# IziDAP-MainSheet.net
KiCad netlist of a schematic drawn in Altium Designer
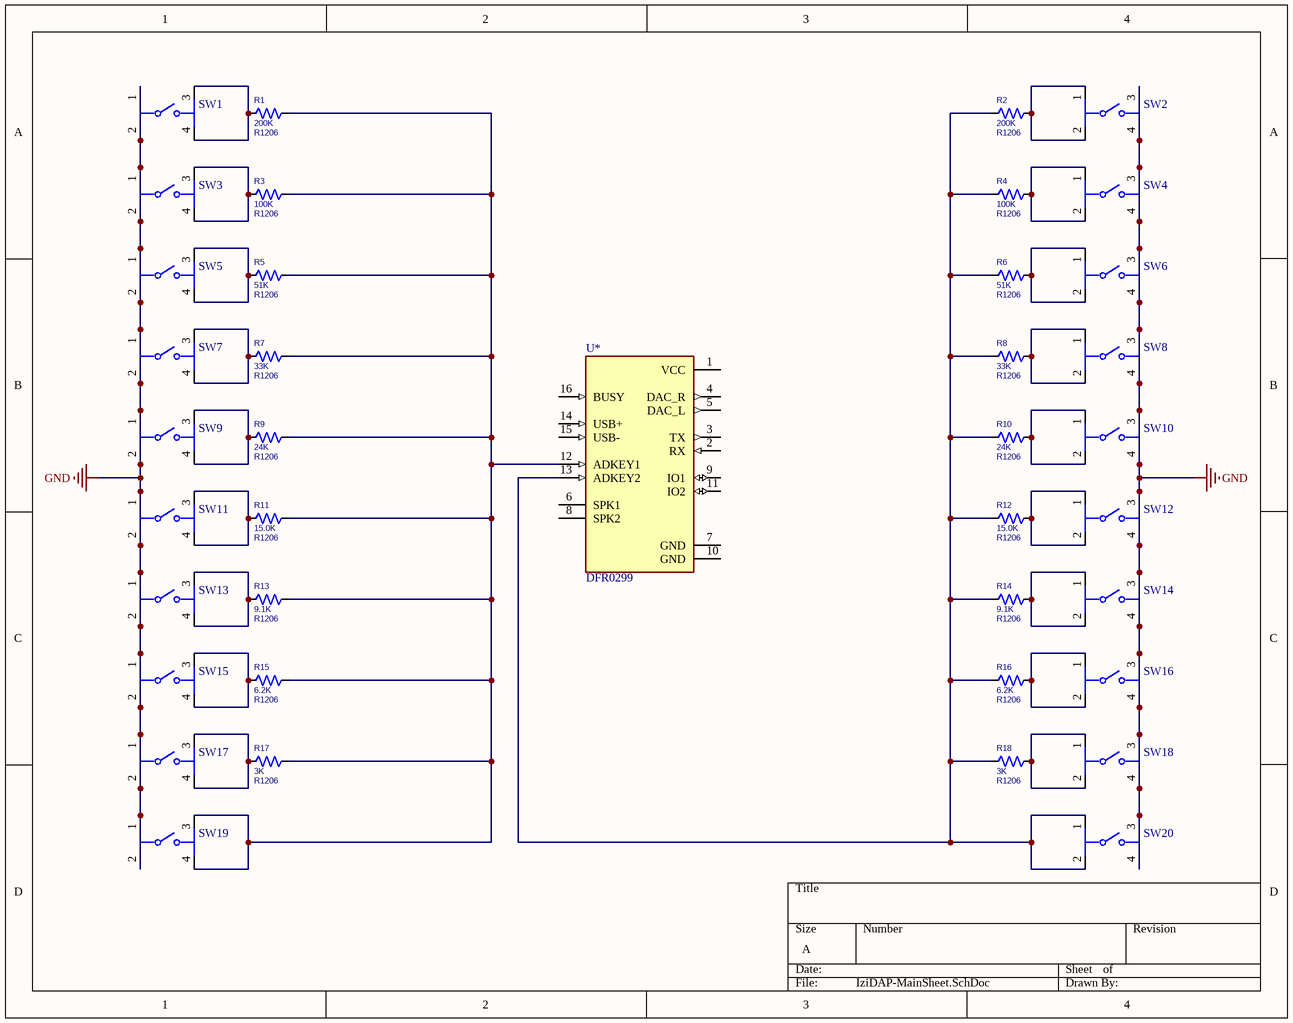
[diagram p0: IziDAP-MainSheet.SchDoc]

(export (version "E")
  (design (tool "Eeschema 10.0.6"))
  (components
    (comp (ref "R1")
      (value "200K")
      (footprint "RESC3216X84N")
      (description "RES, THICK FILM, SMT, 1/4W, 1%, RES1206, 200K")
      (fields
        (field (name "PACKAGE") "R1206")
        (field (name "TOLERANCE") "1%")
        (field (name "MANUFACTURER") "KOA-Speer Electronics, Inc.")
      )
      (libsource (lib "Avidyne") (part "Resistor"))
    )
    (comp (ref "R2")
      (value "200K")
      (footprint "RESC3216X84N")
      (description "RES, THICK FILM, SMT, 1/4W, 1%, RES1206, 200K")
      (fields
        (field (name "PACKAGE") "R1206")
        (field (name "TOLERANCE") "1%")
        (field (name "MANUFACTURER") "KOA-Speer Electronics, Inc.")
      )
      (libsource (lib "Avidyne") (part "Resistor"))
    )
    (comp (ref "R3")
      (value "100K")
      (footprint "RESC3216X84N")
      (description "RES, THICK FILM CHIP, SMT, 1/8W, 1%, RES1206, 100K OHM")
      (fields
        (field (name "PACKAGE") "R1206")
        (field (name "TOLERANCE") "1%")
        (field (name "MANUFACTURER") "Panasonic Electronic Devices, Corp.")
      )
      (libsource (lib "Avidyne") (part "Resistor"))
    )
    (comp (ref "R4")
      (value "100K")
      (footprint "RESC3216X84N")
      (description "RES, THICK FILM CHIP, SMT, 1/8W, 1%, RES1206, 100K OHM")
      (fields
        (field (name "PACKAGE") "R1206")
        (field (name "TOLERANCE") "1%")
        (field (name "MANUFACTURER") "Panasonic Electronic Devices, Corp.")
      )
      (libsource (lib "Avidyne") (part "Resistor"))
    )
    (comp (ref "R5")
      (value "51K")
      (footprint "RESC3216X84N")
      (description "RES, THICK FILM, SMT, 1/8W, 5%, 1206, 51K OHM")
      (fields
        (field (name "PACKAGE") "R1206")
        (field (name "TOLERANCE") "5%")
        (field (name "MANUFACTURER") "Vishay-Dale Intertechnology, Inc")
      )
      (libsource (lib "Avidyne") (part "Resistor"))
    )
    (comp (ref "R6")
      (value "51K")
      (footprint "RESC3216X84N")
      (description "RES, THICK FILM, SMT, 1/8W, 5%, 1206, 51K OHM")
      (fields
        (field (name "PACKAGE") "R1206")
        (field (name "TOLERANCE") "5%")
        (field (name "MANUFACTURER") "Vishay-Dale Intertechnology, Inc")
      )
      (libsource (lib "Avidyne") (part "Resistor"))
    )
    (comp (ref "R7")
      (value "33K")
      (footprint "RESC3216X84N")
      (description "RES, 1/8W, 1%, 1206, 33K OHM")
      (fields
        (field (name "PACKAGE") "R1206")
        (field (name "TOLERANCE") "1%")
        (field (name "MANUFACTURER") "Panasonic Electronic Devices, Corp.")
      )
      (libsource (lib "altium-import") (part "root_1_Resistor_"))
    )
    (comp (ref "R8")
      (value "33K")
      (footprint "RESC3216X84N")
      (description "RES, 1/8W, 1%, 1206, 33K OHM")
      (fields
        (field (name "PACKAGE") "R1206")
        (field (name "TOLERANCE") "1%")
        (field (name "MANUFACTURER") "Panasonic Electronic Devices, Corp.")
      )
      (libsource (lib "altium-import") (part "root_1_Resistor_"))
    )
    (comp (ref "R9")
      (value "24K")
      (footprint "RESC3216X84N")
      (description "RES, 1/8W, 1%, 1206, 24K OHM")
      (fields
        (field (name "PACKAGE") "R1206")
        (field (name "TOLERANCE") "1%")
        (field (name "MANUFACTURER") "Panasonic Electronic Devices, Corp.")
      )
      (libsource (lib "altium-import") (part "root_1_Resistor_"))
    )
    (comp (ref "R10")
      (value "24K")
      (footprint "RESC3216X84N")
      (description "RES, 1/8W, 1%, 1206, 24K OHM")
      (fields
        (field (name "PACKAGE") "R1206")
        (field (name "TOLERANCE") "1%")
        (field (name "MANUFACTURER") "Panasonic Electronic Devices, Corp.")
      )
      (libsource (lib "altium-import") (part "root_1_Resistor_"))
    )
    (comp (ref "R11")
      (value "15.0K")
      (footprint "RESC3216X84N")
      (description "RES, 1/8W, 1%, 1206, 15.0K OHM")
      (fields
        (field (name "PACKAGE") "R1206")
        (field (name "TOLERANCE") "1%")
        (field (name "MANUFACTURER") "Panasonic Electronic Devices, Corp.")
      )
      (libsource (lib "Avidyne") (part "Resistor"))
    )
    (comp (ref "R12")
      (value "15.0K")
      (footprint "RESC3216X84N")
      (description "RES, 1/8W, 1%, 1206, 15.0K OHM")
      (fields
        (field (name "PACKAGE") "R1206")
        (field (name "TOLERANCE") "1%")
        (field (name "MANUFACTURER") "Panasonic Electronic Devices, Corp.")
      )
      (libsource (lib "Avidyne") (part "Resistor"))
    )
    (comp (ref "R13")
      (value "9.1K")
      (footprint "RESC3216X84N")
      (description "RES, 1/8W, 1%, 1206, 9.1K OHM")
      (fields
        (field (name "PACKAGE") "R1206")
        (field (name "TOLERANCE") "1%")
        (field (name "MANUFACTURER") "Panasonic Electronic Devices, Corp.")
      )
      (libsource (lib "altium-import") (part "root_1_Resistor_"))
    )
    (comp (ref "R14")
      (value "9.1K")
      (footprint "RESC3216X84N")
      (description "RES, 1/8W, 1%, 1206, 9.1K OHM")
      (fields
        (field (name "PACKAGE") "R1206")
        (field (name "TOLERANCE") "1%")
        (field (name "MANUFACTURER") "Panasonic Electronic Devices, Corp.")
      )
      (libsource (lib "altium-import") (part "root_1_Resistor_"))
    )
    (comp (ref "R15")
      (value "6.2K")
      (footprint "RESC3216X84N")
      (description "RES, 1/8W, 1%, 1206, 6.2K OHM")
      (fields
        (field (name "PACKAGE") "R1206")
        (field (name "TOLERANCE") "1%")
        (field (name "MANUFACTURER") "Panasonic Electronic Devices, Corp.")
      )
      (libsource (lib "altium-import") (part "root_1_Resistor_"))
    )
    (comp (ref "R16")
      (value "6.2K")
      (footprint "RESC3216X84N")
      (description "RES, 1/8W, 1%, 1206, 6.2K OHM")
      (fields
        (field (name "PACKAGE") "R1206")
        (field (name "TOLERANCE") "1%")
        (field (name "MANUFACTURER") "Panasonic Electronic Devices, Corp.")
      )
      (libsource (lib "altium-import") (part "root_1_Resistor_"))
    )
    (comp (ref "R17")
      (value "3K")
      (footprint "RESC3216X84N")
      (description "RES, 1/8W, 1%, 1206, 3K OHM")
      (fields
        (field (name "PACKAGE") "R1206")
        (field (name "TOLERANCE") "1%")
        (field (name "MANUFACTURER") "Panasonic Electronic Devices, Corp.")
      )
      (libsource (lib "altium-import") (part "root_1_Resistor_"))
    )
    (comp (ref "R18")
      (value "3K")
      (footprint "RESC3216X84N")
      (description "RES, 1/8W, 1%, 1206, 3K OHM")
      (fields
        (field (name "PACKAGE") "R1206")
        (field (name "TOLERANCE") "1%")
        (field (name "MANUFACTURER") "Panasonic Electronic Devices, Corp.")
      )
      (libsource (lib "altium-import") (part "root_1_Resistor_"))
    )
    (comp (ref "SW1")
      (value "2-1825910-6")
      (footprint "FP-2-1825910-6-MFG")
      (description "SWITCH TACTILE SPST-NO 0.05A 24V")
      (libsource (lib "Altium Content Vault") (part "b8895f3f4cefb76e1819d2863dba89b"))
    )
    (comp (ref "SW2")
      (value "2-1825910-6")
      (footprint "FP-2-1825910-6-MFG")
      (description "SWITCH TACTILE SPST-NO 0.05A 24V")
      (libsource (lib "Altium Content Vault") (part "b8895f3f4cefb76e1819d2863dba89b"))
    )
    (comp (ref "SW3")
      (value "2-1825910-6")
      (footprint "FP-2-1825910-6-MFG")
      (description "SWITCH TACTILE SPST-NO 0.05A 24V")
      (libsource (lib "Altium Content Vault") (part "b8895f3f4cefb76e1819d2863dba89b"))
    )
    (comp (ref "SW4")
      (value "2-1825910-6")
      (footprint "FP-2-1825910-6-MFG")
      (description "SWITCH TACTILE SPST-NO 0.05A 24V")
      (libsource (lib "Altium Content Vault") (part "b8895f3f4cefb76e1819d2863dba89b"))
    )
    (comp (ref "SW5")
      (value "2-1825910-6")
      (footprint "FP-2-1825910-6-MFG")
      (description "SWITCH TACTILE SPST-NO 0.05A 24V")
      (libsource (lib "Altium Content Vault") (part "b8895f3f4cefb76e1819d2863dba89b"))
    )
    (comp (ref "SW6")
      (value "2-1825910-6")
      (footprint "FP-2-1825910-6-MFG")
      (description "SWITCH TACTILE SPST-NO 0.05A 24V")
      (libsource (lib "Altium Content Vault") (part "b8895f3f4cefb76e1819d2863dba89b"))
    )
    (comp (ref "SW7")
      (value "2-1825910-6")
      (footprint "FP-2-1825910-6-MFG")
      (description "SWITCH TACTILE SPST-NO 0.05A 24V")
      (libsource (lib "Altium Content Vault") (part "b8895f3f4cefb76e1819d2863dba89b"))
    )
    (comp (ref "SW8")
      (value "2-1825910-6")
      (footprint "FP-2-1825910-6-MFG")
      (description "SWITCH TACTILE SPST-NO 0.05A 24V")
      (libsource (lib "Altium Content Vault") (part "b8895f3f4cefb76e1819d2863dba89b"))
    )
    (comp (ref "SW9")
      (value "2-1825910-6")
      (footprint "FP-2-1825910-6-MFG")
      (description "SWITCH TACTILE SPST-NO 0.05A 24V")
      (libsource (lib "Altium Content Vault") (part "b8895f3f4cefb76e1819d2863dba89b"))
    )
    (comp (ref "SW10")
      (value "2-1825910-6")
      (footprint "FP-2-1825910-6-MFG")
      (description "SWITCH TACTILE SPST-NO 0.05A 24V")
      (libsource (lib "Altium Content Vault") (part "b8895f3f4cefb76e1819d2863dba89b"))
    )
    (comp (ref "SW11")
      (value "2-1825910-6")
      (footprint "FP-2-1825910-6-MFG")
      (description "SWITCH TACTILE SPST-NO 0.05A 24V")
      (libsource (lib "Altium Content Vault") (part "b8895f3f4cefb76e1819d2863dba89b"))
    )
    (comp (ref "SW12")
      (value "2-1825910-6")
      (footprint "FP-2-1825910-6-MFG")
      (description "SWITCH TACTILE SPST-NO 0.05A 24V")
      (libsource (lib "Altium Content Vault") (part "b8895f3f4cefb76e1819d2863dba89b"))
    )
    (comp (ref "SW13")
      (value "2-1825910-6")
      (footprint "FP-2-1825910-6-MFG")
      (description "SWITCH TACTILE SPST-NO 0.05A 24V")
      (libsource (lib "Altium Content Vault") (part "b8895f3f4cefb76e1819d2863dba89b"))
    )
    (comp (ref "SW14")
      (value "2-1825910-6")
      (footprint "FP-2-1825910-6-MFG")
      (description "SWITCH TACTILE SPST-NO 0.05A 24V")
      (libsource (lib "Altium Content Vault") (part "b8895f3f4cefb76e1819d2863dba89b"))
    )
    (comp (ref "SW15")
      (value "2-1825910-6")
      (footprint "FP-2-1825910-6-MFG")
      (description "SWITCH TACTILE SPST-NO 0.05A 24V")
      (libsource (lib "Altium Content Vault") (part "b8895f3f4cefb76e1819d2863dba89b"))
    )
    (comp (ref "SW16")
      (value "2-1825910-6")
      (footprint "FP-2-1825910-6-MFG")
      (description "SWITCH TACTILE SPST-NO 0.05A 24V")
      (libsource (lib "Altium Content Vault") (part "b8895f3f4cefb76e1819d2863dba89b"))
    )
    (comp (ref "SW17")
      (value "2-1825910-6")
      (footprint "FP-2-1825910-6-MFG")
      (description "SWITCH TACTILE SPST-NO 0.05A 24V")
      (libsource (lib "Altium Content Vault") (part "b8895f3f4cefb76e1819d2863dba89b"))
    )
    (comp (ref "SW18")
      (value "2-1825910-6")
      (footprint "FP-2-1825910-6-MFG")
      (description "SWITCH TACTILE SPST-NO 0.05A 24V")
      (libsource (lib "Altium Content Vault") (part "b8895f3f4cefb76e1819d2863dba89b"))
    )
    (comp (ref "SW19")
      (value "2-1825910-6")
      (footprint "FP-2-1825910-6-MFG")
      (description "SWITCH TACTILE SPST-NO 0.05A 24V")
      (libsource (lib "Altium Content Vault") (part "b8895f3f4cefb76e1819d2863dba89b"))
    )
    (comp (ref "SW20")
      (value "2-1825910-6")
      (footprint "FP-2-1825910-6-MFG")
      (description "SWITCH TACTILE SPST-NO 0.05A 24V")
      (libsource (lib "Altium Content Vault") (part "b8895f3f4cefb76e1819d2863dba89b"))
    )
    (comp (ref "U*")
      (value "DFR0299")
      (footprint "DFR0299")
      (description "DFRobot DFR0299 DFPlayer - A Mini MP3 Player For Arduino")
      (fields (field (name "MANUFACTURER") "DFRobot"))
      (libsource (lib "Modules") (part "DFR0299"))
    )
  )
  (nets
    (net (code "1") (name "GND") (class "Default")
      (node (ref "SW1") (pin "1") (pinfunction "1_1") (pintype "passive"))
      (node (ref "SW1") (pin "2") (pinfunction "2_2") (pintype "passive"))
      (node (ref "SW10") (pin "3") (pinfunction "3_3") (pintype "passive"))
      (node (ref "SW10") (pin "4") (pinfunction "4_4") (pintype "passive"))
      (node (ref "SW11") (pin "1") (pinfunction "1_1") (pintype "passive"))
      (node (ref "SW11") (pin "2") (pinfunction "2_2") (pintype "passive"))
      (node (ref "SW12") (pin "3") (pinfunction "3_3") (pintype "passive"))
      (node (ref "SW12") (pin "4") (pinfunction "4_4") (pintype "passive"))
      (node (ref "SW13") (pin "1") (pinfunction "1_1") (pintype "passive"))
      (node (ref "SW13") (pin "2") (pinfunction "2_2") (pintype "passive"))
      (node (ref "SW14") (pin "3") (pinfunction "3_3") (pintype "passive"))
      (node (ref "SW14") (pin "4") (pinfunction "4_4") (pintype "passive"))
      (node (ref "SW15") (pin "1") (pinfunction "1_1") (pintype "passive"))
      (node (ref "SW15") (pin "2") (pinfunction "2_2") (pintype "passive"))
      (node (ref "SW16") (pin "3") (pinfunction "3_3") (pintype "passive"))
      (node (ref "SW16") (pin "4") (pinfunction "4_4") (pintype "passive"))
      (node (ref "SW17") (pin "1") (pinfunction "1_1") (pintype "passive"))
      (node (ref "SW17") (pin "2") (pinfunction "2_2") (pintype "passive"))
      (node (ref "SW18") (pin "3") (pinfunction "3_3") (pintype "passive"))
      (node (ref "SW18") (pin "4") (pinfunction "4_4") (pintype "passive"))
      (node (ref "SW19") (pin "1") (pinfunction "1_1") (pintype "passive"))
      (node (ref "SW19") (pin "2") (pinfunction "2_2") (pintype "passive"))
      (node (ref "SW2") (pin "3") (pinfunction "3_3") (pintype "passive"))
      (node (ref "SW2") (pin "4") (pinfunction "4_4") (pintype "passive"))
      (node (ref "SW20") (pin "3") (pinfunction "3_3") (pintype "passive"))
      (node (ref "SW20") (pin "4") (pinfunction "4_4") (pintype "passive"))
      (node (ref "SW3") (pin "1") (pinfunction "1_1") (pintype "passive"))
      (node (ref "SW3") (pin "2") (pinfunction "2_2") (pintype "passive"))
      (node (ref "SW4") (pin "3") (pinfunction "3_3") (pintype "passive"))
      (node (ref "SW4") (pin "4") (pinfunction "4_4") (pintype "passive"))
      (node (ref "SW5") (pin "1") (pinfunction "1_1") (pintype "passive"))
      (node (ref "SW5") (pin "2") (pinfunction "2_2") (pintype "passive"))
      (node (ref "SW6") (pin "3") (pinfunction "3_3") (pintype "passive"))
      (node (ref "SW6") (pin "4") (pinfunction "4_4") (pintype "passive"))
      (node (ref "SW7") (pin "1") (pinfunction "1_1") (pintype "passive"))
      (node (ref "SW7") (pin "2") (pinfunction "2_2") (pintype "passive"))
      (node (ref "SW8") (pin "3") (pinfunction "3_3") (pintype "passive"))
      (node (ref "SW8") (pin "4") (pinfunction "4_4") (pintype "passive"))
      (node (ref "SW9") (pin "1") (pinfunction "1_1") (pintype "passive"))
      (node (ref "SW9") (pin "2") (pinfunction "2_2") (pintype "passive"))
    )
    (net (code "2") (name "Net-(R1-Pad1)") (class "Default")
      (node (ref "R1") (pin "1") (pinfunction "1_1") (pintype "passive"))
      (node (ref "SW1") (pin "3") (pinfunction "3_3") (pintype "passive"))
      (node (ref "SW1") (pin "4") (pinfunction "4_4") (pintype "passive"))
    )
    (net (code "3") (name "Net-(R2-Pad2)") (class "Default")
      (node (ref "R2") (pin "2") (pinfunction "2_2") (pintype "passive"))
      (node (ref "SW2") (pin "1") (pinfunction "1_1") (pintype "passive"))
      (node (ref "SW2") (pin "2") (pinfunction "2_2") (pintype "passive"))
    )
    (net (code "4") (name "Net-(R3-Pad1)") (class "Default")
      (node (ref "R3") (pin "1") (pinfunction "1_1") (pintype "passive"))
      (node (ref "SW3") (pin "3") (pinfunction "3_3") (pintype "passive"))
      (node (ref "SW3") (pin "4") (pinfunction "4_4") (pintype "passive"))
    )
    (net (code "5") (name "Net-(R4-Pad2)") (class "Default")
      (node (ref "R4") (pin "2") (pinfunction "2_2") (pintype "passive"))
      (node (ref "SW4") (pin "1") (pinfunction "1_1") (pintype "passive"))
      (node (ref "SW4") (pin "2") (pinfunction "2_2") (pintype "passive"))
    )
    (net (code "6") (name "Net-(R5-Pad1)") (class "Default")
      (node (ref "R5") (pin "1") (pinfunction "1_1") (pintype "passive"))
      (node (ref "SW5") (pin "3") (pinfunction "3_3") (pintype "passive"))
      (node (ref "SW5") (pin "4") (pinfunction "4_4") (pintype "passive"))
    )
    (net (code "7") (name "Net-(R6-Pad2)") (class "Default")
      (node (ref "R6") (pin "2") (pinfunction "2_2") (pintype "passive"))
      (node (ref "SW6") (pin "1") (pinfunction "1_1") (pintype "passive"))
      (node (ref "SW6") (pin "2") (pinfunction "2_2") (pintype "passive"))
    )
    (net (code "8") (name "Net-(R7-Pad1)") (class "Default")
      (node (ref "R7") (pin "1") (pinfunction "1_1") (pintype "passive"))
      (node (ref "SW7") (pin "3") (pinfunction "3_3") (pintype "passive"))
      (node (ref "SW7") (pin "4") (pinfunction "4_4") (pintype "passive"))
    )
    (net (code "9") (name "Net-(R8-Pad2)") (class "Default")
      (node (ref "R8") (pin "2") (pinfunction "2_2") (pintype "passive"))
      (node (ref "SW8") (pin "1") (pinfunction "1_1") (pintype "passive"))
      (node (ref "SW8") (pin "2") (pinfunction "2_2") (pintype "passive"))
    )
    (net (code "10") (name "Net-(R9-Pad1)") (class "Default")
      (node (ref "R9") (pin "1") (pinfunction "1_1") (pintype "passive"))
      (node (ref "SW9") (pin "3") (pinfunction "3_3") (pintype "passive"))
      (node (ref "SW9") (pin "4") (pinfunction "4_4") (pintype "passive"))
    )
    (net (code "11") (name "Net-(R10-Pad2)") (class "Default")
      (node (ref "R10") (pin "2") (pinfunction "2_2") (pintype "passive"))
      (node (ref "SW10") (pin "1") (pinfunction "1_1") (pintype "passive"))
      (node (ref "SW10") (pin "2") (pinfunction "2_2") (pintype "passive"))
    )
    (net (code "12") (name "Net-(R11-Pad1)") (class "Default")
      (node (ref "R11") (pin "1") (pinfunction "1_1") (pintype "passive"))
      (node (ref "SW11") (pin "3") (pinfunction "3_3") (pintype "passive"))
      (node (ref "SW11") (pin "4") (pinfunction "4_4") (pintype "passive"))
    )
    (net (code "13") (name "Net-(R12-Pad2)") (class "Default")
      (node (ref "R12") (pin "2") (pinfunction "2_2") (pintype "passive"))
      (node (ref "SW12") (pin "1") (pinfunction "1_1") (pintype "passive"))
      (node (ref "SW12") (pin "2") (pinfunction "2_2") (pintype "passive"))
    )
    (net (code "14") (name "Net-(R13-Pad1)") (class "Default")
      (node (ref "R13") (pin "1") (pinfunction "1_1") (pintype "passive"))
      (node (ref "SW13") (pin "3") (pinfunction "3_3") (pintype "passive"))
      (node (ref "SW13") (pin "4") (pinfunction "4_4") (pintype "passive"))
    )
    (net (code "15") (name "Net-(R14-Pad2)") (class "Default")
      (node (ref "R14") (pin "2") (pinfunction "2_2") (pintype "passive"))
      (node (ref "SW14") (pin "1") (pinfunction "1_1") (pintype "passive"))
      (node (ref "SW14") (pin "2") (pinfunction "2_2") (pintype "passive"))
    )
    (net (code "16") (name "Net-(R15-Pad1)") (class "Default")
      (node (ref "R15") (pin "1") (pinfunction "1_1") (pintype "passive"))
      (node (ref "SW15") (pin "3") (pinfunction "3_3") (pintype "passive"))
      (node (ref "SW15") (pin "4") (pinfunction "4_4") (pintype "passive"))
    )
    (net (code "17") (name "Net-(R16-Pad2)") (class "Default")
      (node (ref "R16") (pin "2") (pinfunction "2_2") (pintype "passive"))
      (node (ref "SW16") (pin "1") (pinfunction "1_1") (pintype "passive"))
      (node (ref "SW16") (pin "2") (pinfunction "2_2") (pintype "passive"))
    )
    (net (code "18") (name "Net-(R17-Pad1)") (class "Default")
      (node (ref "R17") (pin "1") (pinfunction "1_1") (pintype "passive"))
      (node (ref "SW17") (pin "3") (pinfunction "3_3") (pintype "passive"))
      (node (ref "SW17") (pin "4") (pinfunction "4_4") (pintype "passive"))
    )
    (net (code "19") (name "Net-(R18-Pad2)") (class "Default")
      (node (ref "R18") (pin "2") (pinfunction "2_2") (pintype "passive"))
      (node (ref "SW18") (pin "1") (pinfunction "1_1") (pintype "passive"))
      (node (ref "SW18") (pin "2") (pinfunction "2_2") (pintype "passive"))
    )
    (net (code "20") (name "Net-(U*-ADKEY1)") (class "Default")
      (node (ref "R1") (pin "2") (pinfunction "2_2") (pintype "passive"))
      (node (ref "R11") (pin "2") (pinfunction "2_2") (pintype "passive"))
      (node (ref "R13") (pin "2") (pinfunction "2_2") (pintype "passive"))
      (node (ref "R15") (pin "2") (pinfunction "2_2") (pintype "passive"))
      (node (ref "R17") (pin "2") (pinfunction "2_2") (pintype "passive"))
      (node (ref "R3") (pin "2") (pinfunction "2_2") (pintype "passive"))
      (node (ref "R5") (pin "2") (pinfunction "2_2") (pintype "passive"))
      (node (ref "R7") (pin "2") (pinfunction "2_2") (pintype "passive"))
      (node (ref "R9") (pin "2") (pinfunction "2_2") (pintype "passive"))
      (node (ref "SW19") (pin "3") (pinfunction "3_3") (pintype "passive"))
      (node (ref "SW19") (pin "4") (pinfunction "4_4") (pintype "passive"))
      (node (ref "U*") (pin "12") (pinfunction "ADKEY1_12") (pintype "input"))
    )
    (net (code "21") (name "Net-(U*-ADKEY2)") (class "Default")
      (node (ref "R10") (pin "1") (pinfunction "1_1") (pintype "passive"))
      (node (ref "R12") (pin "1") (pinfunction "1_1") (pintype "passive"))
      (node (ref "R14") (pin "1") (pinfunction "1_1") (pintype "passive"))
      (node (ref "R16") (pin "1") (pinfunction "1_1") (pintype "passive"))
      (node (ref "R18") (pin "1") (pinfunction "1_1") (pintype "passive"))
      (node (ref "R2") (pin "1") (pinfunction "1_1") (pintype "passive"))
      (node (ref "R4") (pin "1") (pinfunction "1_1") (pintype "passive"))
      (node (ref "R6") (pin "1") (pinfunction "1_1") (pintype "passive"))
      (node (ref "R8") (pin "1") (pinfunction "1_1") (pintype "passive"))
      (node (ref "SW20") (pin "1") (pinfunction "1_1") (pintype "passive"))
      (node (ref "SW20") (pin "2") (pinfunction "2_2") (pintype "passive"))
      (node (ref "U*") (pin "13") (pinfunction "ADKEY2_13") (pintype "input"))
    )
    (net (code "22") (name "unconnected-(U*-BUSY-Pad16)") (class "Default")
      (node (ref "U*") (pin "16") (pinfunction "BUSY_16") (pintype "input"))
    )
    (net (code "23") (name "unconnected-(U*-DAC_L-Pad5)") (class "Default")
      (node (ref "U*") (pin "5") (pinfunction "DAC_L_5") (pintype "output"))
    )
    (net (code "24") (name "unconnected-(U*-DAC_R-Pad4)") (class "Default")
      (node (ref "U*") (pin "4") (pinfunction "DAC_R_4") (pintype "output"))
    )
    (net (code "25") (name "unconnected-(U*-GND-Pad7)") (class "Default")
      (node (ref "U*") (pin "7") (pinfunction "GND_7") (pintype "power_in"))
    )
    (net (code "26") (name "unconnected-(U*-GND-Pad10)") (class "Default")
      (node (ref "U*") (pin "10") (pinfunction "GND_10") (pintype "power_in"))
    )
    (net (code "27") (name "unconnected-(U*-IO1-Pad9)") (class "Default")
      (node (ref "U*") (pin "9") (pinfunction "IO1_9") (pintype "bidirectional"))
    )
    (net (code "28") (name "unconnected-(U*-IO2-Pad11)") (class "Default")
      (node (ref "U*") (pin "11") (pinfunction "IO2_11") (pintype "bidirectional"))
    )
    (net (code "29") (name "unconnected-(U*-RX-Pad2)") (class "Default")
      (node (ref "U*") (pin "2") (pinfunction "RX_2") (pintype "input"))
    )
    (net (code "30") (name "unconnected-(U*-SPK1-Pad6)") (class "Default")
      (node (ref "U*") (pin "6") (pinfunction "SPK1_6") (pintype "passive"))
    )
    (net (code "31") (name "unconnected-(U*-SPK2-Pad8)") (class "Default")
      (node (ref "U*") (pin "8") (pinfunction "SPK2_8") (pintype "passive"))
    )
    (net (code "32") (name "unconnected-(U*-TX-Pad3)") (class "Default")
      (node (ref "U*") (pin "3") (pinfunction "TX_3") (pintype "output"))
    )
    (net (code "33") (name "unconnected-(U*-USB+-Pad14)") (class "Default")
      (node (ref "U*") (pin "14") (pinfunction "USB+_14") (pintype "input"))
    )
    (net (code "34") (name "unconnected-(U*-USB--Pad15)") (class "Default")
      (node (ref "U*") (pin "15") (pinfunction "USB-_15") (pintype "input"))
    )
    (net (code "35") (name "unconnected-(U*-VCC-Pad1)") (class "Default")
      (node (ref "U*") (pin "1") (pinfunction "VCC_1") (pintype "power_in"))
    )
  )
)
